# Delay_Chorus_PT2399_MAIN_v1_1.net
KiCad netlist of a schematic drawn in EAGLE
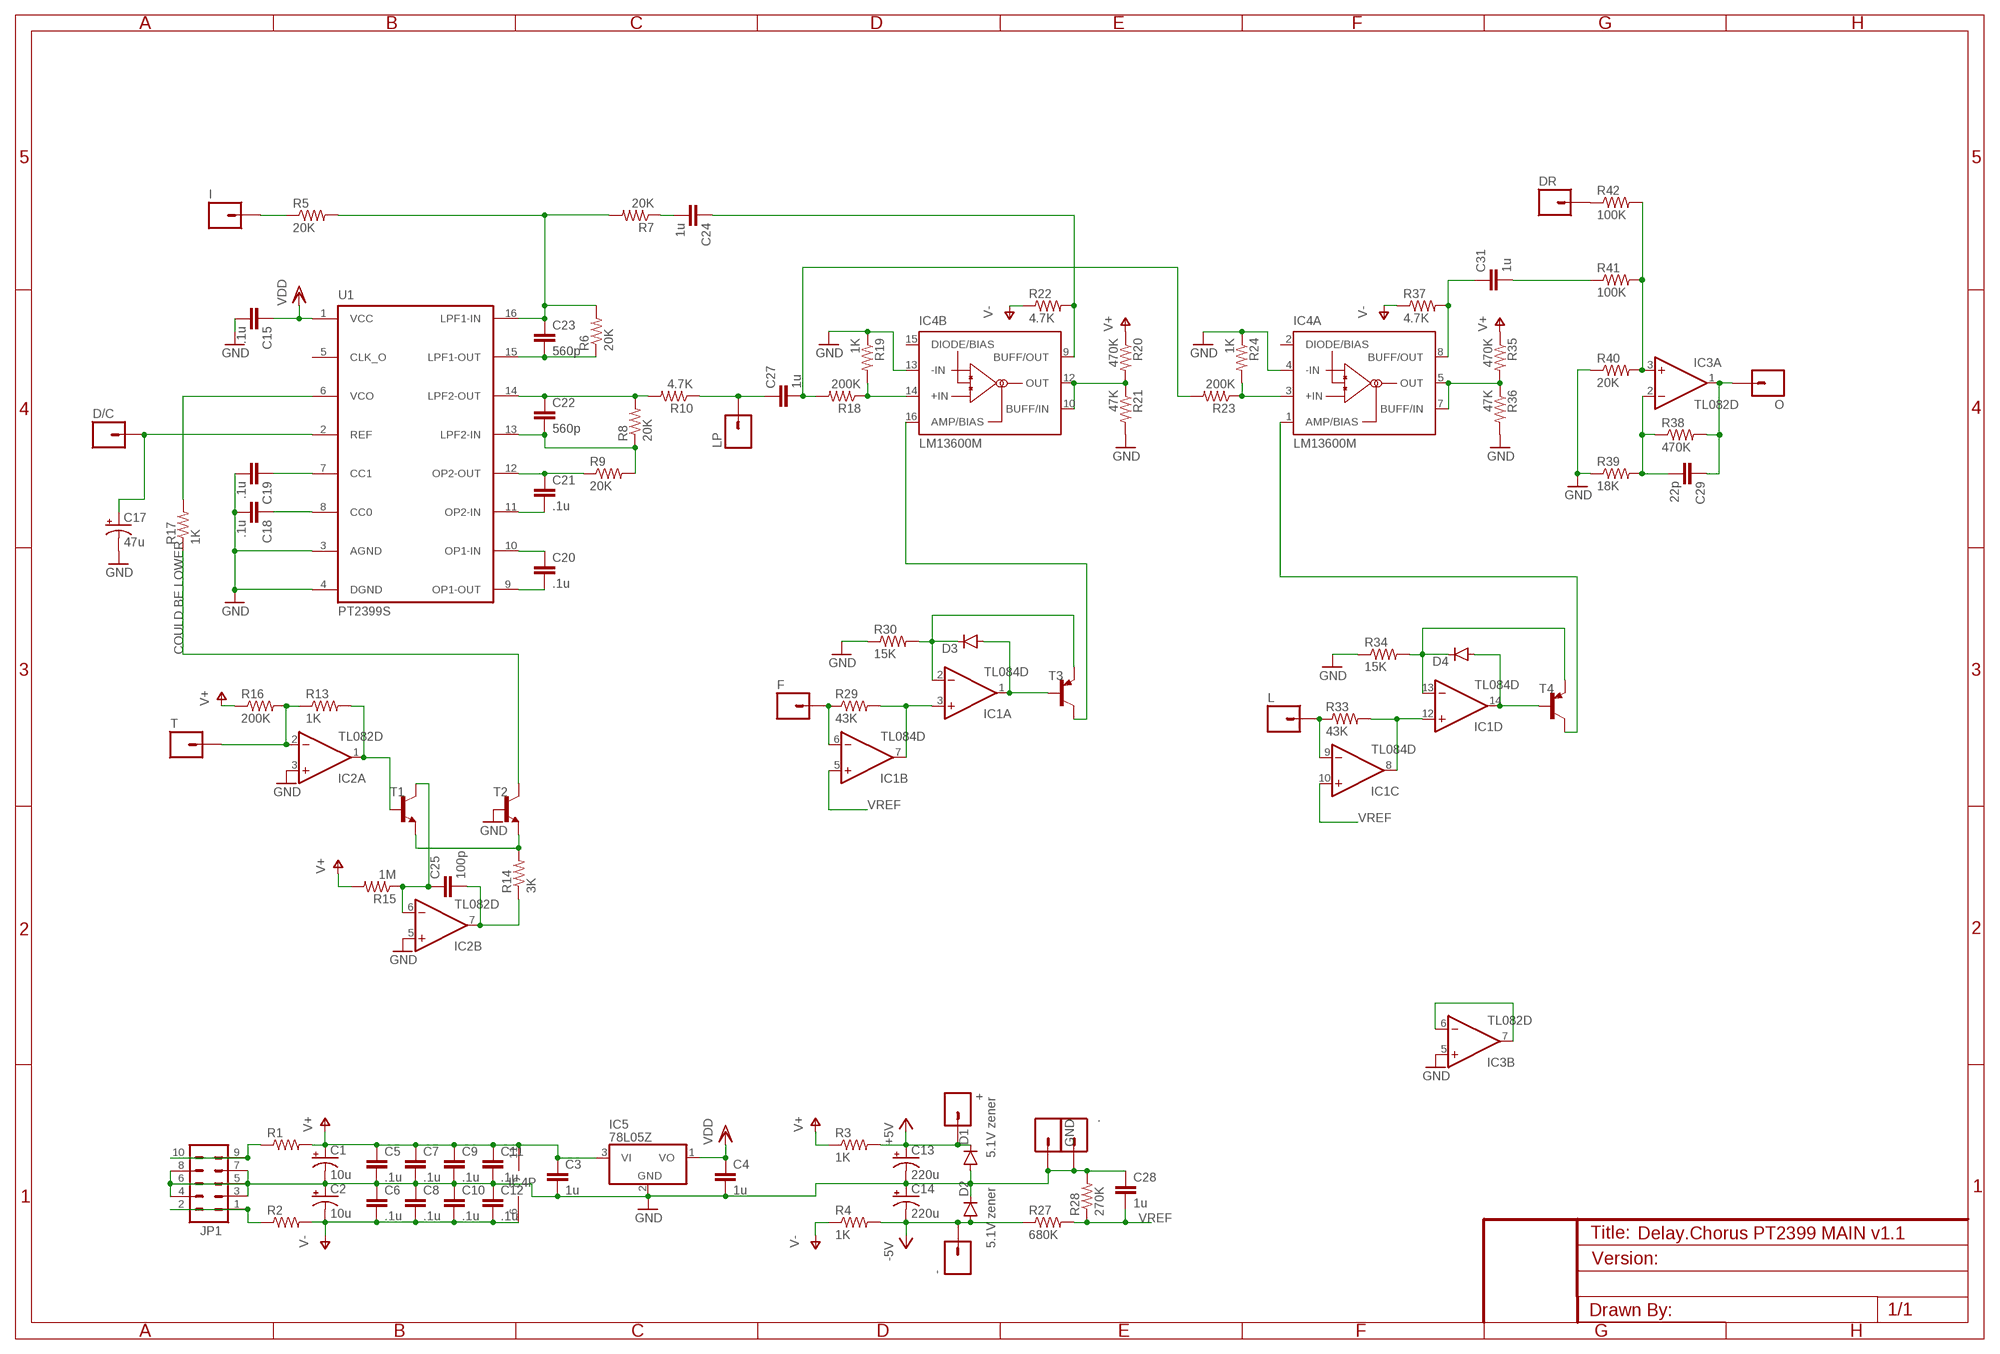
[diagram p0: schematic, sheet 1]

(export (version "E")
  (design (tool "Eeschema 10.0.6"))
  (components
    (comp (ref "+")
      (value "M01PTH")
      (footprint "eagle-import:1X01")
      (libsource (lib "eagle-import") (part "M01PTH"))
    )
    (comp (ref "-")
      (value "M01PTH")
      (footprint "eagle-import:1X01")
      (libsource (lib "eagle-import") (part "M01PTH"))
    )
    (comp (ref ".")
      (value "M01PTH")
      (footprint "eagle-import:1X01")
      (libsource (lib "eagle-import") (part "M01PTH"))
    )
    (comp (ref "C1")
      (value "10u")
      (footprint "eagle-import:CPOL-RADIAL-10UF-25V")
      (libsource (lib "eagle-import") (part "CAP_POLPTH2"))
    )
    (comp (ref "C2")
      (value "10u")
      (footprint "eagle-import:CPOL-RADIAL-10UF-25V")
      (libsource (lib "eagle-import") (part "CAP_POLPTH2"))
    )
    (comp (ref "C3")
      (value "1u")
      (footprint "eagle-import:0805")
      (libsource (lib "eagle-import") (part "CAP0805"))
    )
    (comp (ref "C4")
      (value "1u")
      (footprint "eagle-import:0805")
      (libsource (lib "eagle-import") (part "CAP0805"))
    )
    (comp (ref "C5")
      (value ".1u")
      (footprint "eagle-import:0805")
      (libsource (lib "eagle-import") (part "CAP0805"))
    )
    (comp (ref "C6")
      (value ".1u")
      (footprint "eagle-import:0805")
      (libsource (lib "eagle-import") (part "CAP0805"))
    )
    (comp (ref "C7")
      (value ".1u")
      (footprint "eagle-import:0805")
      (libsource (lib "eagle-import") (part "CAP0805"))
    )
    (comp (ref "C8")
      (value ".1u")
      (footprint "eagle-import:0805")
      (libsource (lib "eagle-import") (part "CAP0805"))
    )
    (comp (ref "C9")
      (value ".1u")
      (footprint "eagle-import:0805")
      (libsource (lib "eagle-import") (part "CAP0805"))
    )
    (comp (ref "C10")
      (value ".1u")
      (footprint "eagle-import:0805")
      (libsource (lib "eagle-import") (part "CAP0805"))
    )
    (comp (ref "C11")
      (value ".1u")
      (footprint "eagle-import:0805")
      (libsource (lib "eagle-import") (part "CAP0805"))
    )
    (comp (ref "C12")
      (value ".1u")
      (footprint "eagle-import:0805")
      (libsource (lib "eagle-import") (part "CAP0805"))
    )
    (comp (ref "C13")
      (value "220u")
      (footprint "eagle-import:E2,5-5")
      (libsource (lib "eagle-import") (part "CPOL-USE2.5-5"))
    )
    (comp (ref "C14")
      (value "220u")
      (footprint "eagle-import:E2,5-5")
      (libsource (lib "eagle-import") (part "CPOL-USE2.5-5"))
    )
    (comp (ref "C15")
      (value ".1u")
      (footprint "eagle-import:0805")
      (libsource (lib "eagle-import") (part "CAP0805"))
    )
    (comp (ref "C17")
      (value "47u")
      (footprint "eagle-import:E2,5-5")
      (libsource (lib "eagle-import") (part "CPOL-USE2.5-5"))
    )
    (comp (ref "C18")
      (value ".1u")
      (footprint "eagle-import:0805")
      (libsource (lib "eagle-import") (part "CAP0805"))
    )
    (comp (ref "C19")
      (value ".1u")
      (footprint "eagle-import:0805")
      (libsource (lib "eagle-import") (part "CAP0805"))
    )
    (comp (ref "C20")
      (value ".1u")
      (footprint "eagle-import:0805")
      (libsource (lib "eagle-import") (part "CAP0805"))
    )
    (comp (ref "C21")
      (value ".1u")
      (footprint "eagle-import:0805")
      (libsource (lib "eagle-import") (part "CAP0805"))
    )
    (comp (ref "C22")
      (value "560p")
      (footprint "eagle-import:0805")
      (libsource (lib "eagle-import") (part "CAP0805"))
    )
    (comp (ref "C23")
      (value "560p")
      (footprint "eagle-import:0805")
      (libsource (lib "eagle-import") (part "CAP0805"))
    )
    (comp (ref "C24")
      (value "1u")
      (footprint "eagle-import:0805")
      (libsource (lib "eagle-import") (part "CAP0805"))
    )
    (comp (ref "C25")
      (value "100p")
      (footprint "eagle-import:0805")
      (libsource (lib "eagle-import") (part "CAP0805"))
    )
    (comp (ref "C27")
      (value "1u")
      (footprint "eagle-import:0805")
      (libsource (lib "eagle-import") (part "CAP0805"))
    )
    (comp (ref "C28")
      (value "1u")
      (footprint "eagle-import:0805")
      (libsource (lib "eagle-import") (part "CAP0805"))
    )
    (comp (ref "C29")
      (value "22p")
      (footprint "eagle-import:0805")
      (libsource (lib "eagle-import") (part "CAP0805"))
    )
    (comp (ref "C31")
      (value "1u")
      (footprint "eagle-import:0805")
      (libsource (lib "eagle-import") (part "CAP0805"))
    )
    (comp (ref "D/C")
      (value "M01PTH")
      (footprint "eagle-import:1X01")
      (libsource (lib "eagle-import") (part "M01PTH"))
    )
    (comp (ref "D1")
      (value "5.1V zener")
      (footprint "eagle-import:SOD-123")
      (libsource (lib "eagle-import") (part "DIODESOD123"))
    )
    (comp (ref "D2")
      (value "5.1V zener")
      (footprint "eagle-import:SOD-123")
      (libsource (lib "eagle-import") (part "DIODESOD123"))
    )
    (comp (ref "D3")
      (value "DIODESOD123")
      (footprint "eagle-import:SOD-123")
      (libsource (lib "eagle-import") (part "DIODESOD123"))
    )
    (comp (ref "D4")
      (value "DIODESOD123")
      (footprint "eagle-import:SOD-123")
      (libsource (lib "eagle-import") (part "DIODESOD123"))
    )
    (comp (ref "DR")
      (value "M01PTH")
      (footprint "eagle-import:1X01")
      (libsource (lib "eagle-import") (part "M01PTH"))
    )
    (comp (ref "F")
      (value "M01PTH")
      (footprint "eagle-import:1X01")
      (libsource (lib "eagle-import") (part "M01PTH"))
    )
    (comp (ref "GND")
      (value "M01PTH")
      (footprint "eagle-import:1X01")
      (libsource (lib "eagle-import") (part "M01PTH"))
    )
    (comp (ref "I")
      (value "M01PTH")
      (footprint "eagle-import:1X01")
      (libsource (lib "eagle-import") (part "M01PTH"))
    )
    (comp (ref "IC1")
      (value "TL084D")
      (footprint "eagle-import:SO14")
      (libsource (lib "eagle-import") (part "TL084D"))
    )
    (comp (ref "IC2")
      (value "TL082D")
      (footprint "eagle-import:SO08")
      (libsource (lib "eagle-import") (part "TL082D"))
    )
    (comp (ref "IC3")
      (value "TL082D")
      (footprint "eagle-import:SO08")
      (libsource (lib "eagle-import") (part "TL082D"))
    )
    (comp (ref "IC4")
      (value "LM13600M")
      (footprint "eagle-import:SO16")
      (libsource (lib "eagle-import") (part "LM13600M"))
    )
    (comp (ref "IC5")
      (value "78L05Z")
      (footprint "eagle-import:TO92")
      (libsource (lib "eagle-import") (part "78ZL05"))
    )
    (comp (ref "JP1")
      (value "M05X2PTH")
      (footprint "eagle-import:AVR_ICSP")
      (libsource (lib "eagle-import") (part "M05X2PTH"))
    )
    (comp (ref "L")
      (value "M01PTH")
      (footprint "eagle-import:1X01")
      (libsource (lib "eagle-import") (part "M01PTH"))
    )
    (comp (ref "LP")
      (value "M01PTH")
      (footprint "eagle-import:1X01")
      (libsource (lib "eagle-import") (part "M01PTH"))
    )
    (comp (ref "O")
      (value "M01PTH")
      (footprint "eagle-import:1X01")
      (libsource (lib "eagle-import") (part "M01PTH"))
    )
    (comp (ref "R1")
      (value "RESISTOR0805-RES")
      (footprint "eagle-import:0805")
      (libsource (lib "eagle-import") (part "RESISTOR0805-RES"))
    )
    (comp (ref "R2")
      (value "RESISTOR0805-RES")
      (footprint "eagle-import:0805")
      (libsource (lib "eagle-import") (part "RESISTOR0805-RES"))
    )
    (comp (ref "R3")
      (value "1K")
      (footprint "eagle-import:0805")
      (libsource (lib "eagle-import") (part "RESISTOR0805-RES"))
    )
    (comp (ref "R4")
      (value "1K")
      (footprint "eagle-import:0805")
      (libsource (lib "eagle-import") (part "RESISTOR0805-RES"))
    )
    (comp (ref "R5")
      (value "20K")
      (footprint "eagle-import:0805")
      (libsource (lib "eagle-import") (part "RESISTOR0805-RES"))
    )
    (comp (ref "R6")
      (value "20K")
      (footprint "eagle-import:0805")
      (libsource (lib "eagle-import") (part "RESISTOR0805-RES"))
    )
    (comp (ref "R7")
      (value "20K")
      (footprint "eagle-import:0805")
      (libsource (lib "eagle-import") (part "RESISTOR0805-RES"))
    )
    (comp (ref "R8")
      (value "20K")
      (footprint "eagle-import:0805")
      (libsource (lib "eagle-import") (part "RESISTOR0805-RES"))
    )
    (comp (ref "R9")
      (value "20K")
      (footprint "eagle-import:0805")
      (libsource (lib "eagle-import") (part "RESISTOR0805-RES"))
    )
    (comp (ref "R10")
      (value "4.7K")
      (footprint "eagle-import:0805")
      (libsource (lib "eagle-import") (part "RESISTOR0805-RES"))
    )
    (comp (ref "R13")
      (value "1K")
      (footprint "eagle-import:0805")
      (libsource (lib "eagle-import") (part "RESISTOR0805-RES"))
    )
    (comp (ref "R14")
      (value "3K")
      (footprint "eagle-import:0805")
      (libsource (lib "eagle-import") (part "RESISTOR0805-RES"))
    )
    (comp (ref "R15")
      (value "1M")
      (footprint "eagle-import:0805")
      (libsource (lib "eagle-import") (part "RESISTOR0805-RES"))
    )
    (comp (ref "R16")
      (value "200K")
      (footprint "eagle-import:0805")
      (libsource (lib "eagle-import") (part "RESISTOR0805-RES"))
    )
    (comp (ref "R17")
      (value "1K")
      (footprint "eagle-import:0805")
      (libsource (lib "eagle-import") (part "RESISTOR0805-RES"))
    )
    (comp (ref "R18")
      (value "200K")
      (footprint "eagle-import:0805")
      (libsource (lib "eagle-import") (part "RESISTOR0805-RES"))
    )
    (comp (ref "R19")
      (value "1K")
      (footprint "eagle-import:0805")
      (libsource (lib "eagle-import") (part "RESISTOR0805-RES"))
    )
    (comp (ref "R20")
      (value "470K")
      (footprint "eagle-import:0805")
      (libsource (lib "eagle-import") (part "RESISTOR0805-RES"))
    )
    (comp (ref "R21")
      (value "47K")
      (footprint "eagle-import:0805")
      (libsource (lib "eagle-import") (part "RESISTOR0805-RES"))
    )
    (comp (ref "R22")
      (value "4.7K")
      (footprint "eagle-import:0805")
      (libsource (lib "eagle-import") (part "RESISTOR0805-RES"))
    )
    (comp (ref "R23")
      (value "200K")
      (footprint "eagle-import:0805")
      (libsource (lib "eagle-import") (part "RESISTOR0805-RES"))
    )
    (comp (ref "R24")
      (value "1K")
      (footprint "eagle-import:0805")
      (libsource (lib "eagle-import") (part "RESISTOR0805-RES"))
    )
    (comp (ref "R27")
      (value "680K")
      (footprint "eagle-import:0805")
      (libsource (lib "eagle-import") (part "RESISTOR0805-RES"))
    )
    (comp (ref "R28")
      (value "270K")
      (footprint "eagle-import:0805")
      (libsource (lib "eagle-import") (part "RESISTOR0805-RES"))
    )
    (comp (ref "R29")
      (value "43K")
      (footprint "eagle-import:0805")
      (libsource (lib "eagle-import") (part "RESISTOR0805-RES"))
    )
    (comp (ref "R30")
      (value "15K")
      (footprint "eagle-import:0805")
      (libsource (lib "eagle-import") (part "RESISTOR0805-RES"))
    )
    (comp (ref "R33")
      (value "43K")
      (footprint "eagle-import:0805")
      (libsource (lib "eagle-import") (part "RESISTOR0805-RES"))
    )
    (comp (ref "R34")
      (value "15K")
      (footprint "eagle-import:0805")
      (libsource (lib "eagle-import") (part "RESISTOR0805-RES"))
    )
    (comp (ref "R35")
      (value "470K")
      (footprint "eagle-import:0805")
      (libsource (lib "eagle-import") (part "RESISTOR0805-RES"))
    )
    (comp (ref "R36")
      (value "47K")
      (footprint "eagle-import:0805")
      (libsource (lib "eagle-import") (part "RESISTOR0805-RES"))
    )
    (comp (ref "R37")
      (value "4.7K")
      (footprint "eagle-import:0805")
      (libsource (lib "eagle-import") (part "RESISTOR0805-RES"))
    )
    (comp (ref "R38")
      (value "470K")
      (footprint "eagle-import:0805")
      (libsource (lib "eagle-import") (part "RESISTOR0805-RES"))
    )
    (comp (ref "R39")
      (value "18K")
      (footprint "eagle-import:0805")
      (libsource (lib "eagle-import") (part "RESISTOR0805-RES"))
    )
    (comp (ref "R40")
      (value "20K")
      (footprint "eagle-import:0805")
      (libsource (lib "eagle-import") (part "RESISTOR0805-RES"))
    )
    (comp (ref "R41")
      (value "100K")
      (footprint "eagle-import:0805")
      (libsource (lib "eagle-import") (part "RESISTOR0805-RES"))
    )
    (comp (ref "R42")
      (value "100K")
      (footprint "eagle-import:0805")
      (libsource (lib "eagle-import") (part "RESISTOR0805-RES"))
    )
    (comp (ref "T")
      (value "M01PTH")
      (footprint "eagle-import:1X01")
      (libsource (lib "eagle-import") (part "M01PTH"))
    )
    (comp (ref "T1")
      (value "MMBT3904LT1-NPN-SOT23-BEC")
      (footprint "eagle-import:SOT23-BEC")
      (libsource (lib "eagle-import") (part "-NPN-SOT23-BECMMBT3904LT1"))
    )
    (comp (ref "T2")
      (value "MMBT3904LT1-NPN-SOT23-BEC")
      (footprint "eagle-import:SOT23-BEC")
      (libsource (lib "eagle-import") (part "-NPN-SOT23-BECMMBT3904LT1"))
    )
    (comp (ref "T3")
      (value "MMBT3906LT1-PNP-SOT23-BEC")
      (footprint "eagle-import:SOT23-BEC")
      (libsource (lib "eagle-import") (part "-PNP-SOT23-BECMMBT3906LT1"))
    )
    (comp (ref "T4")
      (value "MMBT3906LT1-PNP-SOT23-BEC")
      (footprint "eagle-import:SOT23-BEC")
      (libsource (lib "eagle-import") (part "-PNP-SOT23-BECMMBT3906LT1"))
    )
    (comp (ref "U1")
      (value "PT2399S")
      (footprint "eagle-import:SO16W")
      (libsource (lib "eagle-import") (part "PT2399S"))
    )
  )
  (nets
    (net (code "1") (name "+5V") (class "Default")
      (node (ref "+") (pin "1") (pinfunction "1_1") (pintype "passive"))
      (node (ref "C13") (pin "+") (pinfunction "+_+") (pintype "passive"))
      (node (ref "D1") (pin "C") (pinfunction "C_C") (pintype "passive"))
      (node (ref "R3") (pin "2") (pinfunction "2_2") (pintype "passive"))
    )
    (net (code "2") (name "-5V") (class "Default")
      (node (ref "-") (pin "1") (pinfunction "1_1") (pintype "passive"))
      (node (ref "C14") (pin "-") (pinfunction "-_-") (pintype "passive"))
      (node (ref "D2") (pin "A") (pinfunction "A_A") (pintype "passive"))
      (node (ref "R27") (pin "1") (pinfunction "1_1") (pintype "passive"))
      (node (ref "R4") (pin "2") (pinfunction "2_2") (pintype "passive"))
    )
    (net (code "3") (name "/VREF") (class "Default")
      (node (ref "C28") (pin "2") (pinfunction "2_2") (pintype "passive"))
      (node (ref "IC1") (pin "10") (pinfunction "+IN_10") (pintype "input"))
      (node (ref "IC1") (pin "5") (pinfunction "+IN_5") (pintype "input"))
      (node (ref "R27") (pin "2") (pinfunction "2_2") (pintype "passive"))
      (node (ref "R28") (pin "1") (pinfunction "1_1") (pintype "passive"))
    )
    (net (code "4") (name "GND") (class "Default")
      (node (ref ".") (pin "1") (pinfunction "1_1") (pintype "passive"))
      (node (ref "C1") (pin "2") (pinfunction "-_2") (pintype "passive"))
      (node (ref "C10") (pin "1") (pinfunction "1_1") (pintype "passive"))
      (node (ref "C11") (pin "2") (pinfunction "2_2") (pintype "passive"))
      (node (ref "C12") (pin "1") (pinfunction "1_1") (pintype "passive"))
      (node (ref "C13") (pin "-") (pinfunction "-_-") (pintype "passive"))
      (node (ref "C14") (pin "+") (pinfunction "+_+") (pintype "passive"))
      (node (ref "C15") (pin "2") (pinfunction "2_2") (pintype "passive"))
      (node (ref "C17") (pin "-") (pinfunction "-_-") (pintype "passive"))
      (node (ref "C18") (pin "2") (pinfunction "2_2") (pintype "passive"))
      (node (ref "C19") (pin "2") (pinfunction "2_2") (pintype "passive"))
      (node (ref "C2") (pin "1") (pinfunction "+_1") (pintype "passive"))
      (node (ref "C28") (pin "1") (pinfunction "1_1") (pintype "passive"))
      (node (ref "C3") (pin "2") (pinfunction "2_2") (pintype "passive"))
      (node (ref "C4") (pin "2") (pinfunction "2_2") (pintype "passive"))
      (node (ref "C5") (pin "2") (pinfunction "2_2") (pintype "passive"))
      (node (ref "C6") (pin "1") (pinfunction "1_1") (pintype "passive"))
      (node (ref "C7") (pin "2") (pinfunction "2_2") (pintype "passive"))
      (node (ref "C8") (pin "1") (pinfunction "1_1") (pintype "passive"))
      (node (ref "C9") (pin "2") (pinfunction "2_2") (pintype "passive"))
      (node (ref "D1") (pin "A") (pinfunction "A_A") (pintype "passive"))
      (node (ref "D2") (pin "C") (pinfunction "C_C") (pintype "passive"))
      (node (ref "GND") (pin "1") (pinfunction "1_1") (pintype "passive"))
      (node (ref "IC2") (pin "3") (pinfunction "+IN_3") (pintype "input"))
      (node (ref "IC2") (pin "5") (pinfunction "+IN_5") (pintype "input"))
      (node (ref "IC3") (pin "5") (pinfunction "+IN_5") (pintype "input"))
      (node (ref "IC4") (pin "13") (pinfunction "-IN_13") (pintype "input"))
      (node (ref "IC4") (pin "4") (pinfunction "-IN_4") (pintype "input"))
      (node (ref "IC5") (pin "2") (pinfunction "GND_2") (pintype "passive"))
      (node (ref "JP1") (pin "3") (pinfunction "3_3") (pintype "passive"))
      (node (ref "JP1") (pin "4") (pinfunction "4_4") (pintype "passive"))
      (node (ref "JP1") (pin "5") (pinfunction "5_5") (pintype "passive"))
      (node (ref "JP1") (pin "6") (pinfunction "6_6") (pintype "passive"))
      (node (ref "JP1") (pin "7") (pinfunction "7_7") (pintype "passive"))
      (node (ref "JP1") (pin "8") (pinfunction "8_8") (pintype "passive"))
      (node (ref "R19") (pin "1") (pinfunction "1_1") (pintype "passive"))
      (node (ref "R21") (pin "2") (pinfunction "2_2") (pintype "passive"))
      (node (ref "R24") (pin "1") (pinfunction "1_1") (pintype "passive"))
      (node (ref "R28") (pin "2") (pinfunction "2_2") (pintype "passive"))
      (node (ref "R30") (pin "1") (pinfunction "1_1") (pintype "passive"))
      (node (ref "R34") (pin "1") (pinfunction "1_1") (pintype "passive"))
      (node (ref "R36") (pin "2") (pinfunction "2_2") (pintype "passive"))
      (node (ref "R39") (pin "1") (pinfunction "1_1") (pintype "passive"))
      (node (ref "R40") (pin "1") (pinfunction "1_1") (pintype "passive"))
      (node (ref "T2") (pin "B") (pinfunction "B_B") (pintype "passive"))
      (node (ref "U1") (pin "3") (pinfunction "AGND_3") (pintype "power_in"))
      (node (ref "U1") (pin "4") (pinfunction "DGND_4") (pintype "power_in"))
    )
    (net (code "5") (name "Net-(C24-Pad2)") (class "Default")
      (node (ref "C24") (pin "2") (pinfunction "2_2") (pintype "passive"))
      (node (ref "R7") (pin "1") (pinfunction "1_1") (pintype "passive"))
    )
    (net (code "6") (name "Net-(C27-Pad1)") (class "Default")
      (node (ref "C27") (pin "1") (pinfunction "1_1") (pintype "passive"))
      (node (ref "LP") (pin "1") (pinfunction "1_1") (pintype "passive"))
      (node (ref "R10") (pin "1") (pinfunction "1_1") (pintype "passive"))
    )
    (net (code "7") (name "Net-(C27-Pad2)") (class "Default")
      (node (ref "C27") (pin "2") (pinfunction "2_2") (pintype "passive"))
      (node (ref "R18") (pin "2") (pinfunction "2_2") (pintype "passive"))
      (node (ref "R23") (pin "2") (pinfunction "2_2") (pintype "passive"))
    )
    (net (code "8") (name "Net-(C31-Pad2)") (class "Default")
      (node (ref "C31") (pin "2") (pinfunction "2_2") (pintype "passive"))
      (node (ref "R41") (pin "1") (pinfunction "1_1") (pintype "passive"))
    )
    (net (code "9") (name "Net-(DR-Pad1)") (class "Default")
      (node (ref "DR") (pin "1") (pinfunction "1_1") (pintype "passive"))
      (node (ref "R42") (pin "1") (pinfunction "1_1") (pintype "passive"))
    )
    (net (code "10") (name "Net-(I-Pad1)") (class "Default")
      (node (ref "I") (pin "1") (pinfunction "1_1") (pintype "passive"))
      (node (ref "R5") (pin "1") (pinfunction "1_1") (pintype "passive"))
    )
    (net (code "11") (name "Net-(IC1A-+IN)") (class "Default")
      (node (ref "IC1") (pin "3") (pinfunction "+IN_3") (pintype "input"))
      (node (ref "IC1") (pin "7") (pinfunction "OUT_7") (pintype "output"))
      (node (ref "R29") (pin "2") (pinfunction "2_2") (pintype "passive"))
    )
    (net (code "12") (name "Net-(IC1A--IN)") (class "Default")
      (node (ref "D3") (pin "C") (pinfunction "C_C") (pintype "passive"))
      (node (ref "IC1") (pin "2") (pinfunction "-IN_2") (pintype "input"))
      (node (ref "R30") (pin "2") (pinfunction "2_2") (pintype "passive"))
      (node (ref "T3") (pin "E") (pinfunction "E_E") (pintype "passive"))
    )
    (net (code "13") (name "Net-(IC1A-OUT)") (class "Default")
      (node (ref "D3") (pin "A") (pinfunction "A_A") (pintype "passive"))
      (node (ref "IC1") (pin "1") (pinfunction "OUT_1") (pintype "output"))
      (node (ref "T3") (pin "B") (pinfunction "B_B") (pintype "passive"))
    )
    (net (code "14") (name "Net-(IC1B--IN)") (class "Default")
      (node (ref "F") (pin "1") (pinfunction "1_1") (pintype "passive"))
      (node (ref "IC1") (pin "6") (pinfunction "-IN_6") (pintype "input"))
      (node (ref "R29") (pin "1") (pinfunction "1_1") (pintype "passive"))
    )
    (net (code "15") (name "Net-(IC1C--IN)") (class "Default")
      (node (ref "IC1") (pin "9") (pinfunction "-IN_9") (pintype "input"))
      (node (ref "L") (pin "1") (pinfunction "1_1") (pintype "passive"))
      (node (ref "R33") (pin "1") (pinfunction "1_1") (pintype "passive"))
    )
    (net (code "16") (name "Net-(IC1C-OUT)") (class "Default")
      (node (ref "IC1") (pin "12") (pinfunction "+IN_12") (pintype "input"))
      (node (ref "IC1") (pin "8") (pinfunction "OUT_8") (pintype "output"))
      (node (ref "R33") (pin "2") (pinfunction "2_2") (pintype "passive"))
    )
    (net (code "17") (name "Net-(IC1D--IN)") (class "Default")
      (node (ref "D4") (pin "C") (pinfunction "C_C") (pintype "passive"))
      (node (ref "IC1") (pin "13") (pinfunction "-IN_13") (pintype "input"))
      (node (ref "R34") (pin "2") (pinfunction "2_2") (pintype "passive"))
      (node (ref "T4") (pin "E") (pinfunction "E_E") (pintype "passive"))
    )
    (net (code "18") (name "Net-(IC1D-OUT)") (class "Default")
      (node (ref "D4") (pin "A") (pinfunction "A_A") (pintype "passive"))
      (node (ref "IC1") (pin "14") (pinfunction "OUT_14") (pintype "output"))
      (node (ref "T4") (pin "B") (pinfunction "B_B") (pintype "passive"))
    )
    (net (code "19") (name "Net-(IC2A--IN)") (class "Default")
      (node (ref "IC2") (pin "2") (pinfunction "-IN_2") (pintype "input"))
      (node (ref "R13") (pin "1") (pinfunction "1_1") (pintype "passive"))
      (node (ref "R16") (pin "2") (pinfunction "2_2") (pintype "passive"))
      (node (ref "T") (pin "1") (pinfunction "1_1") (pintype "passive"))
    )
    (net (code "20") (name "Net-(IC2A-OUT)") (class "Default")
      (node (ref "IC2") (pin "1") (pinfunction "OUT_1") (pintype "output"))
      (node (ref "R13") (pin "2") (pinfunction "2_2") (pintype "passive"))
      (node (ref "T1") (pin "B") (pinfunction "B_B") (pintype "passive"))
    )
    (net (code "21") (name "Net-(IC2B--IN)") (class "Default")
      (node (ref "C25") (pin "1") (pinfunction "1_1") (pintype "passive"))
      (node (ref "IC2") (pin "6") (pinfunction "-IN_6") (pintype "input"))
      (node (ref "R15") (pin "1") (pinfunction "1_1") (pintype "passive"))
      (node (ref "T1") (pin "C") (pinfunction "C_C") (pintype "passive"))
    )
    (net (code "22") (name "Net-(IC2B-OUT)") (class "Default")
      (node (ref "C25") (pin "2") (pinfunction "2_2") (pintype "passive"))
      (node (ref "IC2") (pin "7") (pinfunction "OUT_7") (pintype "output"))
      (node (ref "R14") (pin "1") (pinfunction "1_1") (pintype "passive"))
    )
    (net (code "23") (name "Net-(IC3A-+IN)") (class "Default")
      (node (ref "IC3") (pin "3") (pinfunction "+IN_3") (pintype "input"))
      (node (ref "R40") (pin "2") (pinfunction "2_2") (pintype "passive"))
      (node (ref "R41") (pin "2") (pinfunction "2_2") (pintype "passive"))
      (node (ref "R42") (pin "2") (pinfunction "2_2") (pintype "passive"))
    )
    (net (code "24") (name "Net-(IC3A--IN)") (class "Default")
      (node (ref "C29") (pin "2") (pinfunction "2_2") (pintype "passive"))
      (node (ref "IC3") (pin "2") (pinfunction "-IN_2") (pintype "input"))
      (node (ref "R38") (pin "1") (pinfunction "1_1") (pintype "passive"))
      (node (ref "R39") (pin "2") (pinfunction "2_2") (pintype "passive"))
    )
    (net (code "25") (name "Net-(IC3A-OUT)") (class "Default")
      (node (ref "C29") (pin "1") (pinfunction "1_1") (pintype "passive"))
      (node (ref "IC3") (pin "1") (pinfunction "OUT_1") (pintype "output"))
      (node (ref "O") (pin "1") (pinfunction "1_1") (pintype "passive"))
      (node (ref "R38") (pin "2") (pinfunction "2_2") (pintype "passive"))
    )
    (net (code "26") (name "Net-(IC3B--IN)") (class "Default")
      (node (ref "IC3") (pin "6") (pinfunction "-IN_6") (pintype "input"))
      (node (ref "IC3") (pin "7") (pinfunction "OUT_7") (pintype "output"))
    )
    (net (code "27") (name "Net-(IC4A-+IN)") (class "Default")
      (node (ref "IC4") (pin "3") (pinfunction "+IN_3") (pintype "input"))
      (node (ref "R23") (pin "1") (pinfunction "1_1") (pintype "passive"))
      (node (ref "R24") (pin "2") (pinfunction "2_2") (pintype "passive"))
    )
    (net (code "28") (name "Net-(IC4A-AMP{slash}BIAS)") (class "Default")
      (node (ref "IC4") (pin "1") (pinfunction "AMP/BIAS_1") (pintype "passive"))
      (node (ref "T4") (pin "C") (pinfunction "C_C") (pintype "passive"))
    )
    (net (code "29") (name "Net-(IC4A-BUFF{slash}IN)") (class "Default")
      (node (ref "IC4") (pin "5") (pinfunction "OUT_5") (pintype "output"))
      (node (ref "IC4") (pin "7") (pinfunction "BUFF/IN_7") (pintype "input"))
      (node (ref "R35") (pin "2") (pinfunction "2_2") (pintype "passive"))
      (node (ref "R36") (pin "1") (pinfunction "1_1") (pintype "passive"))
    )
    (net (code "30") (name "Net-(IC4A-BUFF{slash}OUT)") (class "Default")
      (node (ref "C31") (pin "1") (pinfunction "1_1") (pintype "passive"))
      (node (ref "IC4") (pin "8") (pinfunction "BUFF/OUT_8") (pintype "output"))
      (node (ref "R37") (pin "2") (pinfunction "2_2") (pintype "passive"))
    )
    (net (code "31") (name "Net-(IC4B-+IN)") (class "Default")
      (node (ref "IC4") (pin "14") (pinfunction "+IN_14") (pintype "input"))
      (node (ref "R18") (pin "1") (pinfunction "1_1") (pintype "passive"))
      (node (ref "R19") (pin "2") (pinfunction "2_2") (pintype "passive"))
    )
    (net (code "32") (name "Net-(IC4B-AMP{slash}BIAS)") (class "Default")
      (node (ref "IC4") (pin "16") (pinfunction "AMP/BIAS_16") (pintype "passive"))
      (node (ref "T3") (pin "C") (pinfunction "C_C") (pintype "passive"))
    )
    (net (code "33") (name "Net-(IC4B-BUFF{slash}IN)") (class "Default")
      (node (ref "IC4") (pin "10") (pinfunction "BUFF/IN_10") (pintype "input"))
      (node (ref "IC4") (pin "12") (pinfunction "OUT_12") (pintype "output"))
      (node (ref "R20") (pin "2") (pinfunction "2_2") (pintype "passive"))
      (node (ref "R21") (pin "1") (pinfunction "1_1") (pintype "passive"))
    )
    (net (code "34") (name "Net-(IC4B-BUFF{slash}OUT)") (class "Default")
      (node (ref "C24") (pin "1") (pinfunction "1_1") (pintype "passive"))
      (node (ref "IC4") (pin "9") (pinfunction "BUFF/OUT_9") (pintype "output"))
      (node (ref "R22") (pin "2") (pinfunction "2_2") (pintype "passive"))
    )
    (net (code "35") (name "Net-(JP1-Pad1)") (class "Default")
      (node (ref "JP1") (pin "1") (pinfunction "1_1") (pintype "passive"))
      (node (ref "JP1") (pin "2") (pinfunction "2_2") (pintype "passive"))
      (node (ref "R2") (pin "1") (pinfunction "1_1") (pintype "passive"))
    )
    (net (code "36") (name "Net-(JP1-Pad10)") (class "Default")
      (node (ref "JP1") (pin "10") (pinfunction "10_10") (pintype "passive"))
      (node (ref "JP1") (pin "9") (pinfunction "9_9") (pintype "passive"))
      (node (ref "R1") (pin "1") (pinfunction "1_1") (pintype "passive"))
    )
    (net (code "37") (name "Net-(R14-Pad2)") (class "Default")
      (node (ref "R14") (pin "2") (pinfunction "2_2") (pintype "passive"))
      (node (ref "T1") (pin "E") (pinfunction "E_E") (pintype "passive"))
      (node (ref "T2") (pin "E") (pinfunction "E_E") (pintype "passive"))
    )
    (net (code "38") (name "Net-(R17-Pad1)") (class "Default")
      (node (ref "R17") (pin "1") (pinfunction "1_1") (pintype "passive"))
      (node (ref "T2") (pin "C") (pinfunction "C_C") (pintype "passive"))
    )
    (net (code "39") (name "Net-(U1-CC0)") (class "Default")
      (node (ref "C18") (pin "1") (pinfunction "1_1") (pintype "passive"))
      (node (ref "U1") (pin "8") (pinfunction "CC0_8") (pintype "input"))
    )
    (net (code "40") (name "Net-(U1-CC1)") (class "Default")
      (node (ref "C19") (pin "1") (pinfunction "1_1") (pintype "passive"))
      (node (ref "U1") (pin "7") (pinfunction "CC1_7") (pintype "input"))
    )
    (net (code "41") (name "Net-(U1-LPF1-IN)") (class "Default")
      (node (ref "C23") (pin "1") (pinfunction "1_1") (pintype "passive"))
      (node (ref "R5") (pin "2") (pinfunction "2_2") (pintype "passive"))
      (node (ref "R6") (pin "2") (pinfunction "2_2") (pintype "passive"))
      (node (ref "R7") (pin "2") (pinfunction "2_2") (pintype "passive"))
      (node (ref "U1") (pin "16") (pinfunction "LPF1-IN_16") (pintype "input"))
    )
    (net (code "42") (name "Net-(U1-LPF1-OUT)") (class "Default")
      (node (ref "C23") (pin "2") (pinfunction "2_2") (pintype "passive"))
      (node (ref "R6") (pin "1") (pinfunction "1_1") (pintype "passive"))
      (node (ref "U1") (pin "15") (pinfunction "LPF1-OUT_15") (pintype "output"))
    )
    (net (code "43") (name "Net-(U1-LPF2-IN)") (class "Default")
      (node (ref "C22") (pin "2") (pinfunction "2_2") (pintype "passive"))
      (node (ref "R8") (pin "1") (pinfunction "1_1") (pintype "passive"))
      (node (ref "R9") (pin "2") (pinfunction "2_2") (pintype "passive"))
      (node (ref "U1") (pin "13") (pinfunction "LPF2-IN_13") (pintype "input"))
    )
    (net (code "44") (name "Net-(U1-LPF2-OUT)") (class "Default")
      (node (ref "C22") (pin "1") (pinfunction "1_1") (pintype "passive"))
      (node (ref "R10") (pin "2") (pinfunction "2_2") (pintype "passive"))
      (node (ref "R8") (pin "2") (pinfunction "2_2") (pintype "passive"))
      (node (ref "U1") (pin "14") (pinfunction "LPF2-OUT_14") (pintype "output"))
    )
    (net (code "45") (name "Net-(U1-OP1-IN)") (class "Default")
      (node (ref "C20") (pin "1") (pinfunction "1_1") (pintype "passive"))
      (node (ref "U1") (pin "10") (pinfunction "OP1-IN_10") (pintype "input"))
    )
    (net (code "46") (name "Net-(U1-OP1-OUT)") (class "Default")
      (node (ref "C20") (pin "2") (pinfunction "2_2") (pintype "passive"))
      (node (ref "U1") (pin "9") (pinfunction "OP1-OUT_9") (pintype "output"))
    )
    (net (code "47") (name "Net-(U1-OP2-IN)") (class "Default")
      (node (ref "C21") (pin "2") (pinfunction "2_2") (pintype "passive"))
      (node (ref "U1") (pin "11") (pinfunction "OP2-IN_11") (pintype "input"))
    )
    (net (code "48") (name "Net-(U1-OP2-OUT)") (class "Default")
      (node (ref "C21") (pin "1") (pinfunction "1_1") (pintype "passive"))
      (node (ref "R9") (pin "1") (pinfunction "1_1") (pintype "passive"))
      (node (ref "U1") (pin "12") (pinfunction "OP2-OUT_12") (pintype "output"))
    )
    (net (code "49") (name "Net-(U1-REF)") (class "Default")
      (node (ref "C17") (pin "+") (pinfunction "+_+") (pintype "passive"))
      (node (ref "D/C") (pin "1") (pinfunction "1_1") (pintype "passive"))
      (node (ref "U1") (pin "2") (pinfunction "REF_2") (pintype "input"))
    )
    (net (code "50") (name "Net-(U1-VCO)") (class "Default")
      (node (ref "R17") (pin "2") (pinfunction "2_2") (pintype "passive"))
      (node (ref "U1") (pin "6") (pinfunction "VCO_6") (pintype "input"))
    )
    (net (code "51") (name "V+") (class "Default")
      (node (ref "C1") (pin "1") (pinfunction "+_1") (pintype "passive"))
      (node (ref "C11") (pin "1") (pinfunction "1_1") (pintype "passive"))
      (node (ref "C3") (pin "1") (pinfunction "1_1") (pintype "passive"))
      (node (ref "C5") (pin "1") (pinfunction "1_1") (pintype "passive"))
      (node (ref "C7") (pin "1") (pinfunction "1_1") (pintype "passive"))
      (node (ref "C9") (pin "1") (pinfunction "1_1") (pintype "passive"))
      (node (ref "IC4") (pin "11") (pinfunction "V+_11") (pintype "power_in"))
      (node (ref "IC5") (pin "3") (pinfunction "VI_3") (pintype "input"))
      (node (ref "R1") (pin "2") (pinfunction "2_2") (pintype "passive"))
      (node (ref "R15") (pin "2") (pinfunction "2_2") (pintype "passive"))
      (node (ref "R16") (pin "1") (pinfunction "1_1") (pintype "passive"))
      (node (ref "R20") (pin "1") (pinfunction "1_1") (pintype "passive"))
      (node (ref "R3") (pin "1") (pinfunction "1_1") (pintype "passive"))
      (node (ref "R35") (pin "1") (pinfunction "1_1") (pintype "passive"))
    )
    (net (code "52") (name "V-") (class "Default")
      (node (ref "C10") (pin "2") (pinfunction "2_2") (pintype "passive"))
      (node (ref "C12") (pin "2") (pinfunction "2_2") (pintype "passive"))
      (node (ref "C2") (pin "2") (pinfunction "-_2") (pintype "passive"))
      (node (ref "C6") (pin "2") (pinfunction "2_2") (pintype "passive"))
      (node (ref "C8") (pin "2") (pinfunction "2_2") (pintype "passive"))
      (node (ref "IC4") (pin "6") (pinfunction "V-_6") (pintype "power_in"))
      (node (ref "R2") (pin "2") (pinfunction "2_2") (pintype "passive"))
      (node (ref "R22") (pin "1") (pinfunction "1_1") (pintype "passive"))
      (node (ref "R37") (pin "1") (pinfunction "1_1") (pintype "passive"))
      (node (ref "R4") (pin "1") (pinfunction "1_1") (pintype "passive"))
    )
    (net (code "53") (name "VDD") (class "Default")
      (node (ref "C15") (pin "1") (pinfunction "1_1") (pintype "passive"))
      (node (ref "C4") (pin "1") (pinfunction "1_1") (pintype "passive"))
      (node (ref "IC5") (pin "1") (pinfunction "VO_1") (pintype "passive"))
      (node (ref "U1") (pin "1") (pinfunction "VCC_1") (pintype "power_in"))
    )
    (net (code "54") (name "unconnected-(IC4A-DIODE{slash}BIAS-Pad2)") (class "Default")
      (node (ref "IC4") (pin "2") (pinfunction "DIODE/BIAS_2") (pintype "passive"))
    )
    (net (code "55") (name "unconnected-(IC4B-DIODE{slash}BIAS-Pad15)") (class "Default")
      (node (ref "IC4") (pin "15") (pinfunction "DIODE/BIAS_15") (pintype "passive"))
    )
    (net (code "56") (name "unconnected-(U1-CLK_O-Pad5)") (class "Default")
      (node (ref "U1") (pin "5") (pinfunction "CLK_O_5") (pintype "output"))
    )
  )
)
